# mLRS-rx-E28-G4-v007.net
KiCad netlist of a schematic drawn in EAGLE
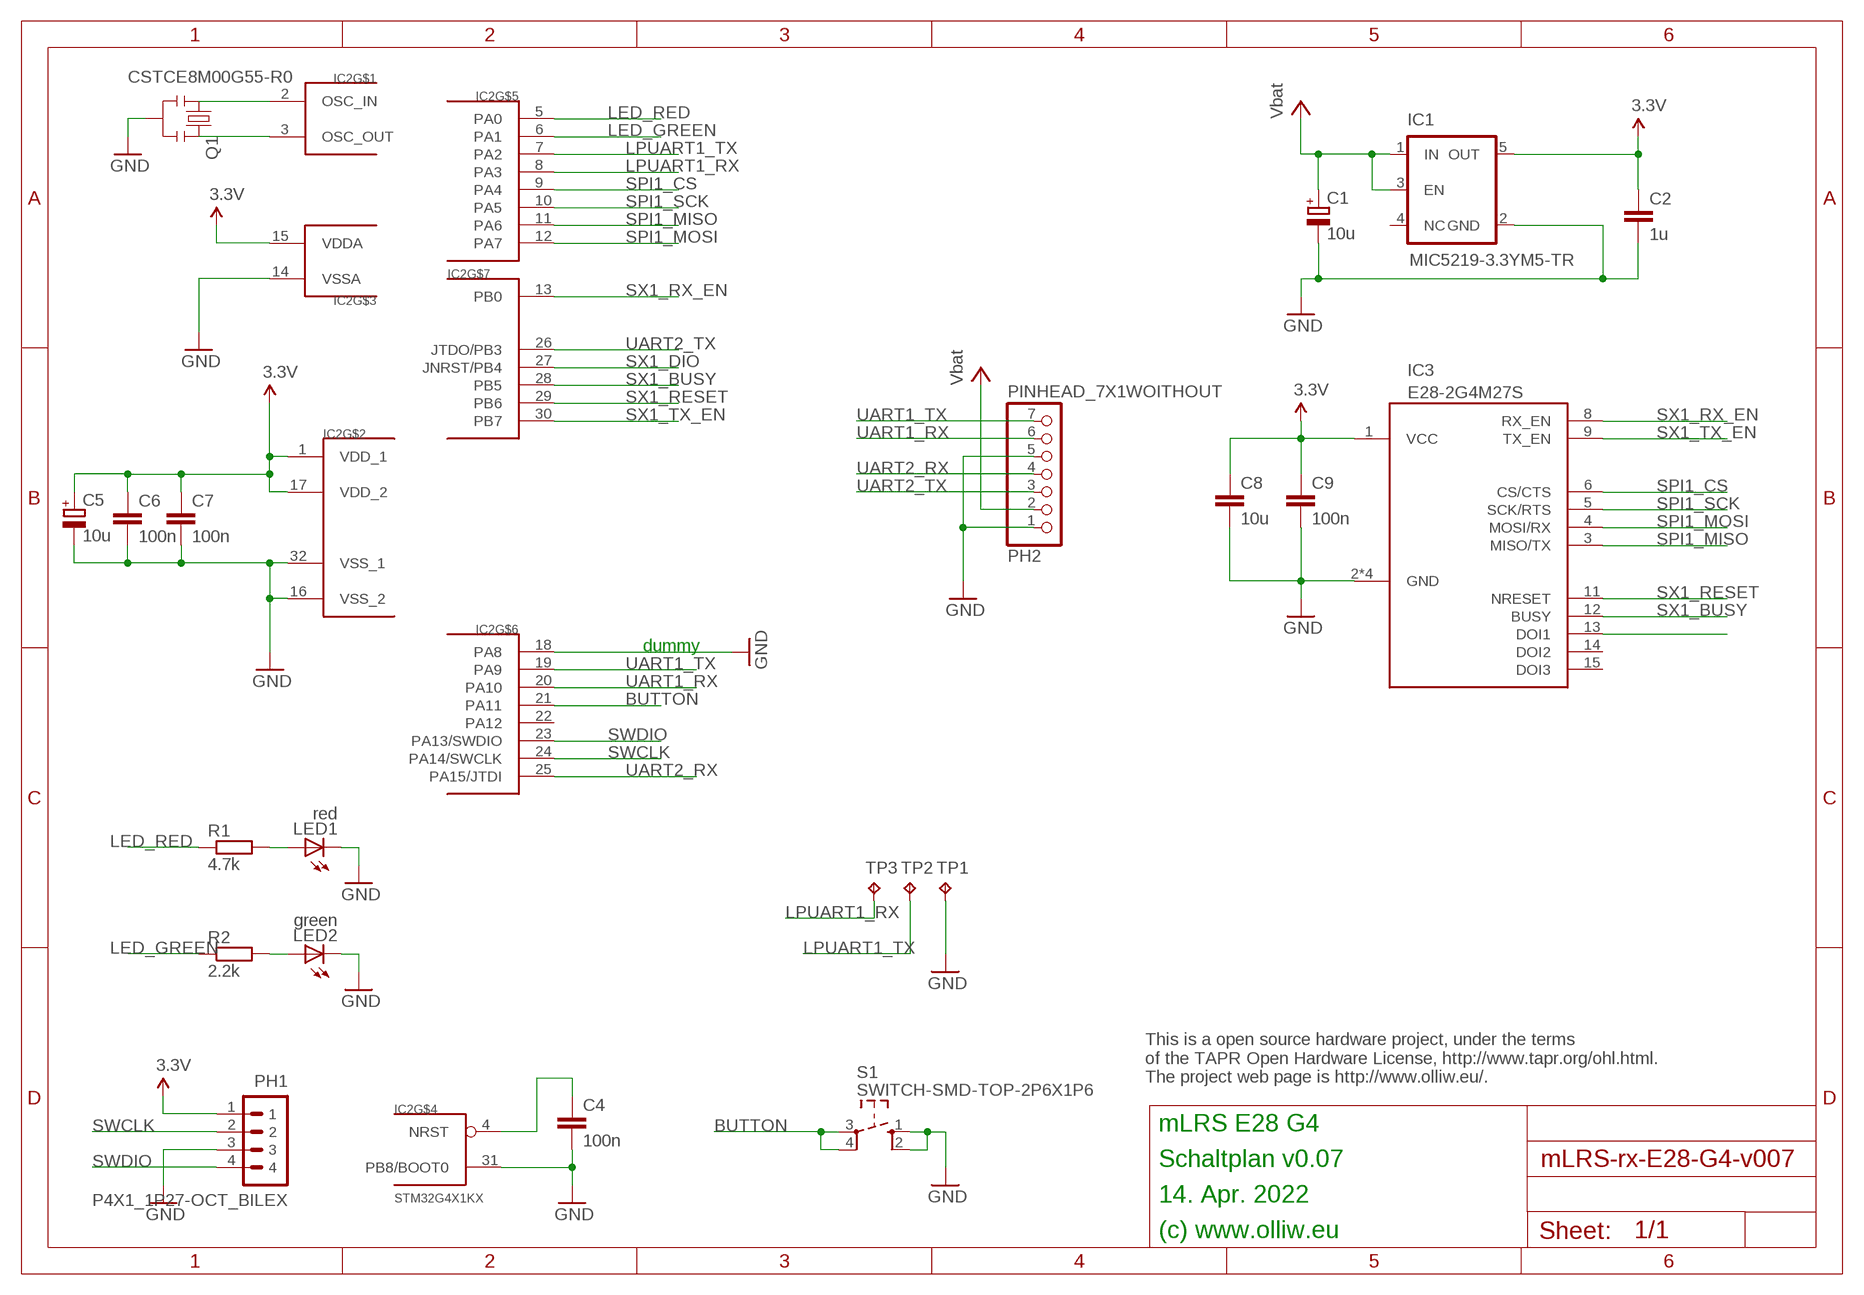
[diagram p0: schematic, sheet 1]

(export (version "E")
  (design (tool "Eeschema 10.0.6"))
  (components
    (comp (ref "C1")
      (value "10u")
      (footprint "eagle-import:SMC_A")
      (libsource (lib "eagle-import") (part "CPOL-EUSMCA"))
    )
    (comp (ref "C2")
      (value "1u")
      (footprint "eagle-import:C0603K")
      (libsource (lib "eagle-import") (part "C-EUC0603K"))
    )
    (comp (ref "C4")
      (value "100n")
      (footprint "eagle-import:C0402")
      (libsource (lib "eagle-import") (part "C-EUC0402"))
    )
    (comp (ref "C5")
      (value "10u")
      (footprint "eagle-import:SMC_A")
      (libsource (lib "eagle-import") (part "CPOL-EUSMCA"))
    )
    (comp (ref "C6")
      (value "100n")
      (footprint "eagle-import:C0402")
      (libsource (lib "eagle-import") (part "C-EUC0402"))
    )
    (comp (ref "C7")
      (value "100n")
      (footprint "eagle-import:C0402")
      (libsource (lib "eagle-import") (part "C-EUC0402"))
    )
    (comp (ref "C8")
      (value "10u")
      (footprint "eagle-import:C0603")
      (libsource (lib "eagle-import") (part "C-EUC0603"))
    )
    (comp (ref "C9")
      (value "100n")
      (footprint "eagle-import:C0402")
      (libsource (lib "eagle-import") (part "C-EUC0402"))
    )
    (comp (ref "IC1")
      (value "MIC5219-3.3YM5-TR")
      (footprint "eagle-import:SOT23-5")
      (libsource (lib "eagle-import") (part "V_REG_TPS76433SOT23-5"))
    )
    (comp (ref "IC2")
      (value "STM32G4X1KX")
      (footprint "eagle-import:UFQFPN32")
      (libsource (lib "eagle-import") (part "STM32G4X1KX"))
    )
    (comp (ref "IC3")
      (value "E28-2G4M27S")
      (footprint "eagle-import:E28-2G4M27")
      (libsource (lib "eagle-import") (part "E28"))
    )
    (comp (ref "LED1")
      (value "red")
      (footprint "eagle-import:CHIPLED_0603")
      (libsource (lib "eagle-import") (part "LEDCHIPLED_0603"))
    )
    (comp (ref "LED2")
      (value "green")
      (footprint "eagle-import:CHIPLED_0603")
      (libsource (lib "eagle-import") (part "LEDCHIPLED_0603"))
    )
    (comp (ref "PH1")
      (value "P4X1_1P27-OCT_BILEX")
      (footprint "eagle-import:4X1_1P27_OCT_BILEX")
      (libsource (lib "eagle-import") (part "P4X1_1P27-OCT_BILEX"))
    )
    (comp (ref "PH2")
      (value "PINHEAD_7X1WOITHOUT")
      (footprint "eagle-import:PINHEAD_7X1_WO")
      (libsource (lib "eagle-import") (part "PINHEAD_7X1WOITHOUT"))
    )
    (comp (ref "Q1")
      (value "CSTCE8M00G55-R0")
      (footprint "eagle-import:RESONATOR-SMD")
      (libsource (lib "eagle-import") (part "RESONATORSMD"))
    )
    (comp (ref "R1")
      (value "4.7k")
      (footprint "eagle-import:R0402")
      (libsource (lib "eagle-import") (part "R-EU_R0402"))
    )
    (comp (ref "R2")
      (value "2.2k")
      (footprint "eagle-import:R0402")
      (libsource (lib "eagle-import") (part "R-EU_R0402"))
    )
    (comp (ref "S1")
      (value "SWITCH-SMD-TOP-2P6X1P6")
      (footprint "eagle-import:TACTILE-SWITCH-SMD-TOP-2P6X1X6")
      (libsource (lib "eagle-import") (part "SWITCH-SMD-TOP-2P6X1P6"))
    )
    (comp (ref "TP1")
      (value "TPB1,27")
      (footprint "eagle-import:B1,27")
      (libsource (lib "eagle-import") (part "TPB1,27"))
    )
    (comp (ref "TP2")
      (value "TPB1,27")
      (footprint "eagle-import:B1,27")
      (libsource (lib "eagle-import") (part "TPB1,27"))
    )
    (comp (ref "TP3")
      (value "TPB1,27")
      (footprint "eagle-import:B1,27")
      (libsource (lib "eagle-import") (part "TPB1,27"))
    )
  )
  (nets
    (net (code "1") (name "/BUTTON") (class "Default")
      (node (ref "IC2") (pin "21") (pinfunction "PA11_21") (pintype "bidirectional"))
      (node (ref "S1") (pin "3") (pinfunction "3_3") (pintype "passive"))
      (node (ref "S1") (pin "4") (pinfunction "4_4") (pintype "passive"))
    )
    (net (code "2") (name "/LED_GREEN") (class "Default")
      (node (ref "IC2") (pin "6") (pinfunction "PA1_6") (pintype "bidirectional"))
      (node (ref "R2") (pin "1") (pinfunction "1_1") (pintype "passive"))
    )
    (net (code "3") (name "/LED_RED") (class "Default")
      (node (ref "IC2") (pin "5") (pinfunction "PA0_5") (pintype "bidirectional"))
      (node (ref "R1") (pin "1") (pinfunction "1_1") (pintype "passive"))
    )
    (net (code "4") (name "/LPUART1_RX") (class "Default")
      (node (ref "IC2") (pin "8") (pinfunction "PA3_8") (pintype "bidirectional"))
      (node (ref "TP3") (pin "TP") (pinfunction "TP_TP") (pintype "input"))
    )
    (net (code "5") (name "/LPUART1_TX") (class "Default")
      (node (ref "IC2") (pin "7") (pinfunction "PA2_7") (pintype "bidirectional"))
      (node (ref "TP2") (pin "TP") (pinfunction "TP_TP") (pintype "input"))
    )
    (net (code "6") (name "/SPI1_CS") (class "Default")
      (node (ref "IC2") (pin "9") (pinfunction "PA4_9") (pintype "bidirectional"))
      (node (ref "IC3") (pin "6") (pinfunction "CS/CTS_6") (pintype "bidirectional"))
    )
    (net (code "7") (name "/SPI1_MISO") (class "Default")
      (node (ref "IC2") (pin "11") (pinfunction "PA6_11") (pintype "bidirectional"))
      (node (ref "IC3") (pin "3") (pinfunction "MISO/TX_3") (pintype "bidirectional"))
    )
    (net (code "8") (name "/SPI1_MOSI") (class "Default")
      (node (ref "IC2") (pin "12") (pinfunction "PA7_12") (pintype "bidirectional"))
      (node (ref "IC3") (pin "4") (pinfunction "MOSI/RX_4") (pintype "bidirectional"))
    )
    (net (code "9") (name "/SPI1_SCK") (class "Default")
      (node (ref "IC2") (pin "10") (pinfunction "PA5_10") (pintype "bidirectional"))
      (node (ref "IC3") (pin "5") (pinfunction "SCK/RTS_5") (pintype "bidirectional"))
    )
    (net (code "10") (name "/SWCLK") (class "Default")
      (node (ref "IC2") (pin "24") (pinfunction "PA14/SWCLK_24") (pintype "bidirectional"))
      (node (ref "PH1") (pin "2") (pinfunction "2_2") (pintype "passive"))
    )
    (net (code "11") (name "/SWDIO") (class "Default")
      (node (ref "IC2") (pin "23") (pinfunction "PA13/SWDIO_23") (pintype "bidirectional"))
      (node (ref "PH1") (pin "4") (pinfunction "4_4") (pintype "passive"))
    )
    (net (code "12") (name "/SX1_BUSY") (class "Default")
      (node (ref "IC2") (pin "28") (pinfunction "PB5_28") (pintype "bidirectional"))
      (node (ref "IC3") (pin "12") (pinfunction "BUSY_12") (pintype "bidirectional"))
    )
    (net (code "13") (name "/SX1_DIO") (class "Default")
      (node (ref "IC2") (pin "27") (pinfunction "JNRST/PB4_27") (pintype "bidirectional"))
      (node (ref "IC3") (pin "13") (pinfunction "DOI1_13") (pintype "bidirectional"))
    )
    (net (code "14") (name "/SX1_RESET") (class "Default")
      (node (ref "IC2") (pin "29") (pinfunction "PB6_29") (pintype "bidirectional"))
      (node (ref "IC3") (pin "11") (pinfunction "NRESET_11") (pintype "input"))
    )
    (net (code "15") (name "/SX1_RX_EN") (class "Default")
      (node (ref "IC2") (pin "13") (pinfunction "PB0_13") (pintype "bidirectional"))
      (node (ref "IC3") (pin "8") (pinfunction "RX_EN_8") (pintype "bidirectional"))
    )
    (net (code "16") (name "/SX1_TX_EN") (class "Default")
      (node (ref "IC2") (pin "30") (pinfunction "PB7_30") (pintype "bidirectional"))
      (node (ref "IC3") (pin "9") (pinfunction "TX_EN_9") (pintype "bidirectional"))
    )
    (net (code "17") (name "/UART1_RX") (class "Default")
      (node (ref "IC2") (pin "20") (pinfunction "PA10_20") (pintype "bidirectional"))
      (node (ref "PH2") (pin "6") (pinfunction "6_6") (pintype "passive"))
    )
    (net (code "18") (name "/UART1_TX") (class "Default")
      (node (ref "IC2") (pin "19") (pinfunction "PA9_19") (pintype "bidirectional"))
      (node (ref "PH2") (pin "7") (pinfunction "7_7") (pintype "passive"))
    )
    (net (code "19") (name "/UART2_RX") (class "Default")
      (node (ref "IC2") (pin "25") (pinfunction "PA15/JTDI_25") (pintype "bidirectional"))
      (node (ref "PH2") (pin "4") (pinfunction "4_4") (pintype "passive"))
    )
    (net (code "20") (name "/UART2_TX") (class "Default")
      (node (ref "IC2") (pin "26") (pinfunction "JTDO/PB3_26") (pintype "bidirectional"))
      (node (ref "PH2") (pin "3") (pinfunction "3_3") (pintype "passive"))
    )
    (net (code "21") (name "3.3V") (class "Default")
      (node (ref "C2") (pin "1") (pinfunction "1_1") (pintype "passive"))
      (node (ref "C5") (pin "+") (pinfunction "+_+") (pintype "passive"))
      (node (ref "C6") (pin "1") (pinfunction "1_1") (pintype "passive"))
      (node (ref "C7") (pin "1") (pinfunction "1_1") (pintype "passive"))
      (node (ref "C8") (pin "1") (pinfunction "1_1") (pintype "passive"))
      (node (ref "C9") (pin "1") (pinfunction "1_1") (pintype "passive"))
      (node (ref "IC1") (pin "5") (pinfunction "OUT_5") (pintype "output"))
      (node (ref "IC2") (pin "1") (pinfunction "VDD_1_1") (pintype "power_in"))
      (node (ref "IC2") (pin "15") (pinfunction "VDDA_15") (pintype "power_in"))
      (node (ref "IC2") (pin "17") (pinfunction "VDD_2_17") (pintype "power_in"))
      (node (ref "IC3") (pin "1") (pinfunction "VCC_1") (pintype "power_in"))
      (node (ref "PH1") (pin "1") (pinfunction "1_1") (pintype "passive"))
    )
    (net (code "22") (name "GND") (class "Default")
      (node (ref "C1") (pin "-") (pinfunction "-_-") (pintype "passive"))
      (node (ref "C2") (pin "2") (pinfunction "2_2") (pintype "passive"))
      (node (ref "C4") (pin "2") (pinfunction "2_2") (pintype "passive"))
      (node (ref "C5") (pin "-") (pinfunction "-_-") (pintype "passive"))
      (node (ref "C6") (pin "2") (pinfunction "2_2") (pintype "passive"))
      (node (ref "C7") (pin "2") (pinfunction "2_2") (pintype "passive"))
      (node (ref "C8") (pin "2") (pinfunction "2_2") (pintype "passive"))
      (node (ref "C9") (pin "2") (pinfunction "2_2") (pintype "passive"))
      (node (ref "IC1") (pin "2") (pinfunction "GND_2") (pintype "power_in"))
      (node (ref "IC2") (pin "14") (pinfunction "VSSA_14") (pintype "power_in"))
      (node (ref "IC2") (pin "16") (pinfunction "VSS_2_16") (pintype "power_in"))
      (node (ref "IC2") (pin "18") (pinfunction "PA8_18") (pintype "bidirectional"))
      (node (ref "IC2") (pin "31") (pinfunction "PB8/BOOT0_31") (pintype "input"))
      (node (ref "IC2") (pin "32") (pinfunction "VSS_1_32") (pintype "power_in"))
      (node (ref "IC3") (pin "10") (pinfunction "GND_10") (pintype "power_in"))
      (node (ref "IC3") (pin "16") (pinfunction "GND_16") (pintype "power_in"))
      (node (ref "IC3") (pin "2") (pinfunction "GND_2") (pintype "power_in"))
      (node (ref "IC3") (pin "7") (pinfunction "GND_7") (pintype "power_in"))
      (node (ref "LED1") (pin "C") (pinfunction "C_C") (pintype "passive"))
      (node (ref "LED2") (pin "C") (pinfunction "C_C") (pintype "passive"))
      (node (ref "PH1") (pin "3") (pinfunction "3_3") (pintype "passive"))
      (node (ref "PH2") (pin "1") (pinfunction "1_1") (pintype "passive"))
      (node (ref "PH2") (pin "5") (pinfunction "5_5") (pintype "passive"))
      (node (ref "Q1") (pin "2") (pinfunction "2_2") (pintype "passive"))
      (node (ref "S1") (pin "1") (pinfunction "1_1") (pintype "passive"))
      (node (ref "S1") (pin "2") (pinfunction "2_2") (pintype "passive"))
      (node (ref "TP1") (pin "TP") (pinfunction "TP_TP") (pintype "input"))
    )
    (net (code "23") (name "Net-(IC2A-OSC_IN)") (class "Default")
      (node (ref "IC2") (pin "2") (pinfunction "OSC_IN_2") (pintype "input"))
      (node (ref "Q1") (pin "1") (pinfunction "1_1") (pintype "passive"))
    )
    (net (code "24") (name "Net-(IC2A-OSC_OUT)") (class "Default")
      (node (ref "IC2") (pin "3") (pinfunction "OSC_OUT_3") (pintype "output"))
      (node (ref "Q1") (pin "3") (pinfunction "3_3") (pintype "passive"))
    )
    (net (code "25") (name "Net-(IC2D-NRST)") (class "Default")
      (node (ref "C4") (pin "1") (pinfunction "1_1") (pintype "passive"))
      (node (ref "IC2") (pin "4") (pinfunction "NRST_4") (pintype "input"))
    )
    (net (code "26") (name "Net-(LED1-PadA)") (class "Default")
      (node (ref "LED1") (pin "A") (pinfunction "A_A") (pintype "passive"))
      (node (ref "R1") (pin "2") (pinfunction "2_2") (pintype "passive"))
    )
    (net (code "27") (name "Net-(LED2-PadA)") (class "Default")
      (node (ref "LED2") (pin "A") (pinfunction "A_A") (pintype "passive"))
      (node (ref "R2") (pin "2") (pinfunction "2_2") (pintype "passive"))
    )
    (net (code "28") (name "Vbat") (class "Default")
      (node (ref "C1") (pin "+") (pinfunction "+_+") (pintype "passive"))
      (node (ref "IC1") (pin "1") (pinfunction "IN_1") (pintype "power_in"))
      (node (ref "IC1") (pin "3") (pinfunction "EN_3") (pintype "input"))
      (node (ref "PH2") (pin "2") (pinfunction "2_2") (pintype "passive"))
    )
    (net (code "29") (name "unconnected-(IC1-NC-Pad4)") (class "Default")
      (node (ref "IC1") (pin "4") (pinfunction "NC_4") (pintype "passive"))
    )
    (net (code "30") (name "unconnected-(IC2F-PA12-Pad22)") (class "Default")
      (node (ref "IC2") (pin "22") (pinfunction "PA12_22") (pintype "bidirectional"))
    )
    (net (code "31") (name "unconnected-(IC3-DOI2-Pad14)") (class "Default")
      (node (ref "IC3") (pin "14") (pinfunction "DOI2_14") (pintype "bidirectional"))
    )
    (net (code "32") (name "unconnected-(IC3-DOI3-Pad15)") (class "Default")
      (node (ref "IC3") (pin "15") (pinfunction "DOI3_15") (pintype "bidirectional"))
    )
  )
)
